# ProPrj_EBS_2026-01-24.net
KiCad netlist of a schematic drawn in EasyEDA Pro
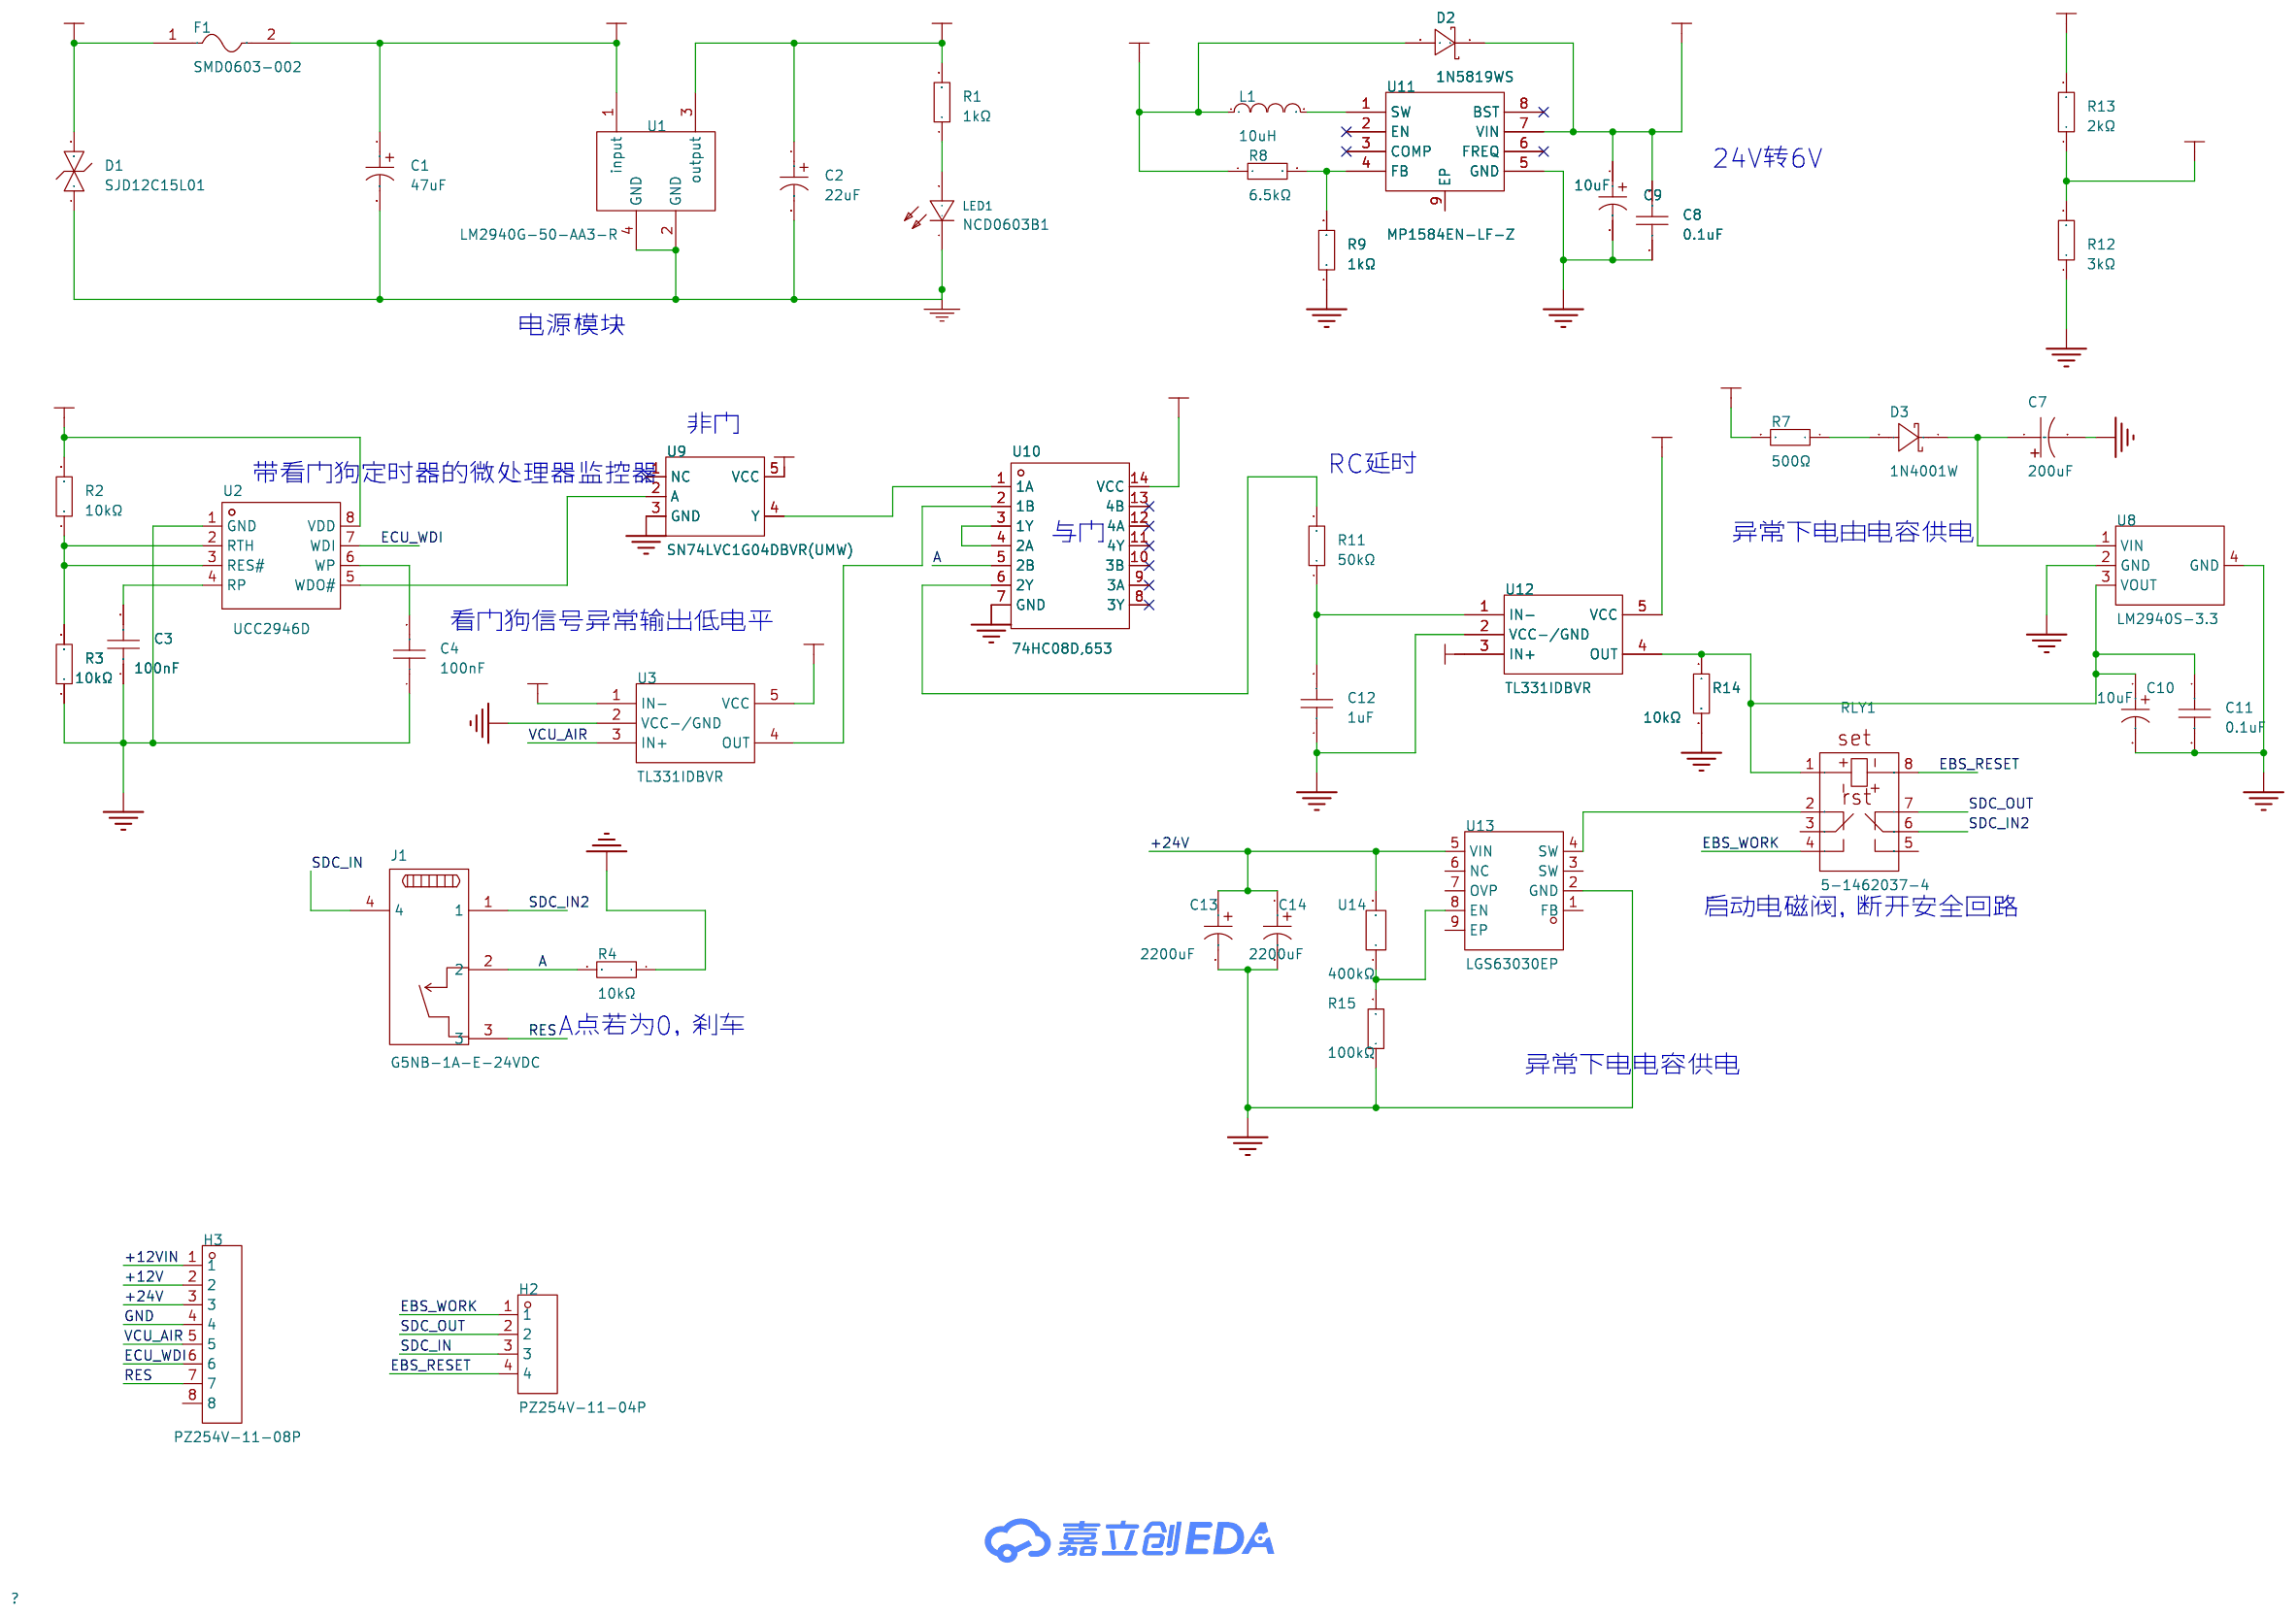
[diagram p0: schematic sheet]

(export (version "E")
  (design (tool "Eeschema 10.0.6"))
  (components
    (comp (ref "C1")
      (value "47uF")
      (footprint "easyedapro:CAP-SMD_BD5.0-L5.3-W5.3-LS5.9-FD")
      (description "容值:47uF;精度:±20%;额定电压:25V;纹波电流:35mA@120Hz;")
      (fields (field (name "Manufacturer Part") "JVJ25V47M5x5") (field (name "Manufacturer") "JIERR(捷而瑞)"))
      (libsource (lib "easyedapro") (part "JVJ25V47M5X5"))
    )
    (comp (ref "C2")
      (value "22uF")
      (footprint "easyedapro:CAP-SMD_BD4.0-L4.3-W4.3-FD_1")
      (description "容值:22uF;精度:±20%;额定电压:16V;纹波电流:20mA@120Hz;")
      (fields (field (name "Manufacturer Part") "JVJ16V22M4X5") (field (name "Manufacturer") "JIERR(捷而瑞)"))
      (libsource (lib "easyedapro") (part "JVJ16V22M4X5"))
    )
    (comp (ref "C3")
      (value "100nF")
      (footprint "easyedapro:C0603")
      (description "容值:100nF;精度:±10%;额定电压:50V;温度系数:X7R;")
      (fields
        (field (name "Manufacturer Part") "CC0603KRX7R9BB104")
        (field (name "Manufacturer") "YAGEO(国巨)")
      )
      (libsource (lib "easyedapro") (part "CC0603KRX7R9BB104"))
    )
    (comp (ref "C4")
      (value "100nF")
      (footprint "easyedapro:C0603")
      (description "容值:100nF;精度:±10%;额定电压:50V;温度系数:X7R;")
      (fields
        (field (name "Manufacturer Part") "CC0603KRX7R9BB104")
        (field (name "Manufacturer") "YAGEO(国巨)")
      )
      (libsource (lib "easyedapro") (part "CC0603KRX7R9BB104"))
    )
    (comp (ref "C7")
      (value "200uF")
      (footprint "easyedapro:CAP-TH_BD12.5-P5.00-D0.6-FD")
      (description "容值:200uF;精度:±20%;额定电压:100V;纹波电流:-;等效串联电阻(ESR):-;")
      (fields (field (name "Manufacturer Part") "LKML1602A201MF") (field (name "Manufacturer") "Ymin(永铭)"))
      (libsource (lib "easyedapro") (part "LKML1602A221MF"))
    )
    (comp (ref "C8")
      (value "0.1uF")
      (footprint "easyedapro:C0603")
      (description "容值:100nF;精度:±10%;额定电压:50V;温度系数:X7R;")
      (fields
        (field (name "Manufacturer Part") "CC0603KRX7R9BB104")
        (field (name "Manufacturer") "YAGEO(国巨)")
      )
      (libsource (lib "easyedapro") (part "CC0603KRX7R9BB104"))
    )
    (comp (ref "C9")
      (value "10uF")
      (footprint "easyedapro:CAP-SMD_BD6.3-L6.6-W6.6-LS7.3-FD-H7.7")
      (description "容值:100uF;精度:±20%;额定电压:50V;纹波电流:140mA@120Hz;")
      (fields (field (name "Manufacturer Part") "JVJ50V100M6x8") (field (name "Manufacturer") "JIERR(捷而瑞)"))
      (libsource (lib "easyedapro") (part "JVJ50V100M6X8"))
    )
    (comp (ref "C10")
      (value "10uF")
      (footprint "easyedapro:CAP-SMD_BD6.3-L6.6-W6.6-LS7.3-FD-H7.7")
      (description "容值:100uF;精度:±20%;额定电压:50V;纹波电流:140mA@120Hz;")
      (fields (field (name "Manufacturer Part") "JVJ50V100M6x8") (field (name "Manufacturer") "JIERR(捷而瑞)"))
      (libsource (lib "easyedapro") (part "JVJ50V100M6X8"))
    )
    (comp (ref "C11")
      (value "0.1uF")
      (footprint "easyedapro:C0603")
      (description "容值:100nF;精度:±10%;额定电压:50V;温度系数:X7R;")
      (fields
        (field (name "Manufacturer Part") "CC0603KRX7R9BB104")
        (field (name "Manufacturer") "YAGEO(国巨)")
      )
      (libsource (lib "easyedapro") (part "CC0603KRX7R9BB104"))
    )
    (comp (ref "C12")
      (value "1uF")
      (footprint "easyedapro:C0603")
      (description "容值:1uF;精度:±10%;额定电压:50V;温度系数:X5R;")
      (fields
        (field (name "Manufacturer Part") "CGA0603X5R105K500JT")
        (field (name "Manufacturer") "HRE(芯声)")
      )
      (libsource (lib "easyedapro") (part "CGA0603X5R105K500JT"))
    )
    (comp (ref "C13")
      (value "2200uF")
      (footprint "easyedapro:CAP-SMD_BD16.0-L17.0-W17.0-FD")
      (description "容值:2200uF;精度:±20%;额定电压:25V;纹波电流:900mA@120Hz;")
      (fields
        (field (name "Manufacturer Part") "JVJ25V2200M16X16")
        (field (name "Manufacturer") "JIERR(捷而瑞)")
      )
      (libsource (lib "easyedapro") (part "JVJ25V2200M16X16"))
    )
    (comp (ref "C14")
      (value "2200uF")
      (footprint "easyedapro:CAP-SMD_BD16.0-L17.0-W17.0-FD")
      (description "容值:2200uF;精度:±20%;额定电压:25V;纹波电流:900mA@120Hz;")
      (fields
        (field (name "Manufacturer Part") "JVJ25V2200M16X16")
        (field (name "Manufacturer") "JIERR(捷而瑞)")
      )
      (libsource (lib "easyedapro") (part "JVJ25V2200M16X16"))
    )
    (comp (ref "D1")
      (value "SJD12C15L01")
      (footprint "easyedapro:SOD-123_L2.7-W1.6-LS3.7-BI")
      (description "反向截止电压(Vrwm):15V;击穿电压(VBR):16.7V;峰值脉冲电流(Ipp)@8/20us:8.2A;钳位电压(Vc)@Ipp:24.4V;")
      (fields (field (name "Manufacturer") "Brightking(君耀电子)"))
      (libsource (lib "easyedapro") (part "SJD12C15L01"))
    )
    (comp (ref "D2")
      (value "1N5819WS")
      (footprint "easyedapro:SOD-323_L1.8-W1.3-LS2.5-RD")
      (description "正向压降(Vf):600mV@1A;直流反向耐压(Vr):40V;整流电流:1A;")
      (fields (field (name "Manufacturer") "Hottech(合科泰)"))
      (libsource (lib "easyedapro") (part "1N5819WS"))
    )
    (comp (ref "D3")
      (value "1N4001W")
      (footprint "easyedapro:SOD-123FL_L2.7-W1.8-LS3.8-RD")
      (description "二极管配置:独立式;正向压降(Vf):1V@1.0A;直流反向耐压(Vr):50V;整流电流:1A;")
      (fields (field (name "Manufacturer") "R+O(宏嘉诚)"))
      (libsource (lib "easyedapro") (part "1N4001W_C18199085"))
    )
    (comp (ref "F1")
      (value "SMD0603-002")
      (footprint "easyedapro:F0603")
      (description "30V,0.02A")
      (fields (field (name "Manufacturer") "台湾陆海"))
      (libsource (lib "easyedapro") (part "SMD0603-002"))
    )
    (comp (ref "H2")
      (value "PZ254V-11-04P")
      (footprint "easyedapro:HDR-TH_4P-P2.54-V-M")
      (fields (field (name "Manufacturer") "XFCN(兴飞)"))
      (libsource (lib "easyedapro") (part "PZ254V-11-04P_C2691448"))
    )
    (comp (ref "H3")
      (value "PZ254V-11-08P")
      (footprint "easyedapro:HDR-TH_8P-P2.54-V-M")
      (fields (field (name "Manufacturer") "XFCN(兴飞)"))
      (libsource (lib "easyedapro") (part "PZ254V-11-08P"))
    )
    (comp (ref "J1")
      (value "G5NB-1A-E-24VDC")
      (footprint "easyedapro:RELAY-TH_G5NB-1A-E-24VDC")
      (description "线圈电压:24V;触点形式:一组常开:1A(单刀单掷-常开);触点容量(电阻负载):5A@250VAC；3A@30VDC;最大切换电压:250V@AC；30V@DC;最大切换电流:5A;")
      (fields (field (name "Manufacturer") "OMRON(欧姆龙)"))
      (libsource (lib "easyedapro") (part "G5NB-1A-E-24VDC"))
    )
    (comp (ref "L1")
      (value "10uH")
      (footprint "easyedapro:IND-SMD_L4.0-W4.0")
      (description "电感值:10uH;精度:±20%;额定电流:2.35A;饱和电流(Isat):3.5A;类型:-;")
      (fields
        (field (name "Manufacturer Part") "FHD4020S-100MT")
        (field (name "Manufacturer") "cjiang(长江微电)")
      )
      (libsource (lib "easyedapro") (part "FHD4020S-100MT"))
    )
    (comp (ref "LED1")
      (value "NCD0603B1")
      (footprint "easyedapro:LED0603-RD")
      (description "发光颜色:蓝灯;")
      (fields (field (name "Manufacturer") "国星光电"))
      (libsource (lib "easyedapro") (part "FC-DA1608BK-470H10"))
    )
    (comp (ref "R1")
      (value "1kΩ")
      (footprint "easyedapro:R0603")
      (description "电阻类型:厚膜电阻;阻值:1kΩ;精度:±1%;功率:100mW;")
      (fields
        (field (name "Manufacturer Part") "0603WAF1001T5E")
        (field (name "Manufacturer") "UNI-ROYAL(厚声)")
      )
      (libsource (lib "easyedapro") (part "0603WAF1001T5E"))
    )
    (comp (ref "R2")
      (value "10kΩ")
      (footprint "easyedapro:R0603")
      (description "电阻类型:厚膜电阻;阻值:10kΩ;精度:±1%;功率:100mW;工作电压:75V;温度系数:±100ppm/°C;")
      (fields
        (field (name "Manufacturer Part") "0603WAF1002T5E")
        (field (name "Manufacturer") "UNI-ROYAL(厚声)")
      )
      (libsource (lib "easyedapro") (part "0603WAF1002T5E"))
    )
    (comp (ref "R3")
      (value "10kΩ")
      (footprint "easyedapro:R0603")
      (description "电阻类型:厚膜电阻;阻值:10kΩ;精度:±1%;功率:100mW;工作电压:75V;温度系数:±100ppm/°C;")
      (fields
        (field (name "Manufacturer Part") "0603WAF1002T5E")
        (field (name "Manufacturer") "UNI-ROYAL(厚声)")
      )
      (libsource (lib "easyedapro") (part "0603WAF1002T5E"))
    )
    (comp (ref "R4")
      (value "10kΩ")
      (footprint "easyedapro:R0603")
      (description "电阻类型:厚膜电阻;阻值:1kΩ;精度:±1%;功率:100mW;")
      (fields
        (field (name "Manufacturer Part") "0603WAF1001T5E")
        (field (name "Manufacturer") "UNI-ROYAL(厚声)")
      )
      (libsource (lib "easyedapro") (part "0603WAF1001T5E"))
    )
    (comp (ref "R7")
      (value "500Ω")
      (footprint "easyedapro:R0603")
      (description "电阻类型:厚膜电阻;阻值:1kΩ;精度:±1%;功率:100mW;")
      (fields
        (field (name "Manufacturer Part") "0603WAF1001T5E")
        (field (name "Manufacturer") "UNI-ROYAL(厚声)")
      )
      (libsource (lib "easyedapro") (part "0603WAF1001T5E"))
    )
    (comp (ref "R8")
      (value "6.5kΩ")
      (footprint "easyedapro:R0603")
      (description "电阻类型:厚膜电阻;阻值:1kΩ;精度:±1%;功率:100mW;")
      (fields
        (field (name "Manufacturer Part") "0603WAF1001T5E")
        (field (name "Manufacturer") "UNI-ROYAL(厚声)")
      )
      (libsource (lib "easyedapro") (part "0603WAF1001T5E"))
    )
    (comp (ref "R9")
      (value "1kΩ")
      (footprint "easyedapro:R0603")
      (description "电阻类型:厚膜电阻;阻值:1kΩ;精度:±1%;功率:100mW;")
      (fields
        (field (name "Manufacturer Part") "0603WAF1001T5E")
        (field (name "Manufacturer") "UNI-ROYAL(厚声)")
      )
      (libsource (lib "easyedapro") (part "0603WAF1001T5E"))
    )
    (comp (ref "R11")
      (value "50kΩ")
      (footprint "easyedapro:R0603")
      (description "电阻类型:薄膜电阻;阻值:50kΩ;精度:±0.1%;功率:62.5mW;工作电压:50V;温度系数:±25ppm/°C;")
      (fields (field (name "Manufacturer Part") "AR03BTC5002A") (field (name "Manufacturer") "Viking(光颉)"))
      (libsource (lib "easyedapro") (part "AR03BTC5002A"))
    )
    (comp (ref "R12")
      (value "3kΩ")
      (footprint "easyedapro:R0603")
      (description "电阻类型:厚膜电阻;阻值:3kΩ;精度:±1%;功率:100mW;工作电压:75V;温度系数:±100ppm/°C;")
      (fields
        (field (name "Manufacturer Part") "0603WAF3001T5E")
        (field (name "Manufacturer") "UNI-ROYAL(厚声)")
      )
      (libsource (lib "easyedapro") (part "0603WAF3001T5E"))
    )
    (comp (ref "R13")
      (value "2kΩ")
      (footprint "easyedapro:R0603")
      (description "电阻类型:厚膜电阻;阻值:2kΩ;精度:±1%;功率:100mW;工作电压:75V;温度系数:±100ppm/°C;")
      (fields
        (field (name "Manufacturer Part") "0603WAF2001T5E")
        (field (name "Manufacturer") "UNI-ROYAL(厚声)")
      )
      (libsource (lib "easyedapro") (part "0603WAF2001T5E"))
    )
    (comp (ref "R14")
      (value "10kΩ")
      (footprint "easyedapro:R0603")
      (description "电阻类型:厚膜电阻;阻值:10kΩ;精度:±1%;功率:100mW;工作电压:75V;温度系数:±100ppm/°C;")
      (fields
        (field (name "Manufacturer Part") "0603WAF1002T5E")
        (field (name "Manufacturer") "UNI-ROYAL(厚声)")
      )
      (libsource (lib "easyedapro") (part "0603WAF1002T5E"))
    )
    (comp (ref "R15")
      (value "100kΩ")
      (footprint "easyedapro:R0603")
      (description "电阻类型:厚膜电阻;阻值:100kΩ;精度:±1%;功率:100mW;工作电压:75V;温度系数:±100ppm/°C;")
      (fields
        (field (name "Manufacturer Part") "0603WAF1003T5E")
        (field (name "Manufacturer") "UNI-ROYAL(厚声)")
      )
      (libsource (lib "easyedapro") (part "0603WAF1003T5E"))
    )
    (comp (ref "RLY1")
      (value "5-1462037-4")
      (footprint "easyedapro:RELAY-SMD_8P-L10.0-W6.0_IM43GR")
      (description "线圈电压:3V;触点形式:两组转换:2C(双刀双掷-转换);触点容量(电阻负载):-;最大切换电压:250V@AC；220V@DC;最大切换电流:2A;")
      (fields (field (name "Manufacturer") "TE Connectivity(泰科电子)"))
      (libsource (lib "easyedapro") (part "5-1462037-4"))
    )
    (comp (ref "U1")
      (value "LM2940G-50-AA3-R")
      (footprint "easyedapro:SOT-223-4_L6.5-W3.5-P2.30-LS7.0-BR")
      (description "输出类型:固定;输出极性:正;输出通道数:1;最大输入电压:26V;输出电压:5V;压差:800mV@(1A);输出电流:1A;电源纹波抑制比(PSRR):72dB@(120Hz);")
      (fields (field (name "Manufacturer") "UTC(友顺)"))
      (libsource (lib "easyedapro") (part "LM2940G-50-AA3-R"))
    )
    (comp (ref "U2")
      (value "UCC2946D")
      (footprint "easyedapro:SOIC-8_L4.9-W3.9-P1.27-LS6.0-BL")
      (description "UCC2946 带看门狗定时器的微处理器监控器")
      (fields (field (name "Manufacturer") "TI(德州仪器)"))
      (libsource (lib "easyedapro") (part "UCC2946D"))
    )
    (comp (ref "U3")
      (value "TL331IDBVR")
      (footprint "easyedapro:SOT-23-5_L3.0-W1.7-P0.95-LS2.8-BR")
      (description "比较器数:单路;输入失调电压(Vos):2mV;输入偏置电流(Ib):25nA;轨到轨:轨到轨输入;")
      (fields (field (name "Manufacturer") "TI(德州仪器)"))
      (libsource (lib "easyedapro") (part "TL331IDBVR"))
    )
    (comp (ref "U8")
      (value "LM2940S-3.3")
      (footprint "easyedapro:SOT-223-3_L6.5-W3.4-P2.30-LS7.0-BR")
      (description "输出类型:固定;工作电压:26V;输出电压:3.3V;输出电流:1A;电源纹波抑制比(PSRR):-;输出极性:正极;")
      (fields (field (name "Manufacturer") "HTC"))
      (libsource (lib "easyedapro") (part "LM2940S-3.3"))
    )
    (comp (ref "U9")
      (value "SN74LVC1G04DBVR(UMW)")
      (footprint "easyedapro:SOT-23-5_L3.0-W1.7-P0.95-LS2.8-BR")
      (description "工作电压:1.65V~5.5V;静态电流(Iq):10uA;")
      (fields (field (name "Manufacturer") "UMW(友台半导体)"))
      (libsource (lib "easyedapro") (part "SN74LVC1G04DBVR_C434067"))
    )
    (comp (ref "U10")
      (value "74HC08D,653")
      (footprint "easyedapro:SOIC-14_L8.7-W3.9-P1.27-LS6.0-BL")
      (description "逻辑类型:与门;通道数:4;工作电压:2V~6V;静态电流(Iq):2uA;传播延迟(tpd):27ns@4.5V,50pF;")
      (fields (field (name "Manufacturer") "Nexperia(安世)"))
      (libsource (lib "easyedapro") (part "74HC08D,653"))
    )
    (comp (ref "U11")
      (value "MP1584EN-LF-Z")
      (footprint "easyedapro:SOIC-8_L5.0-W4.0-P1.27-LS6.0-BL-EP2.0")
      (description "功能类型:降压型;工作电压:4.5V~28V;输出电压:800mV~25V;输出电流:3A;输出类型:可调;")
      (fields (field (name "Manufacturer") "MPS(芯源)"))
      (libsource (lib "easyedapro") (part "MP1584EN-LF-Z"))
    )
    (comp (ref "U12")
      (value "TL331IDBVR")
      (footprint "easyedapro:SOT-23-5_L3.0-W1.7-P0.95-LS2.8-BR")
      (description "比较器数:单路;输入失调电压(Vos):2mV;输入偏置电流(Ib):25nA;轨到轨:轨到轨输入;")
      (fields (field (name "Manufacturer") "TI(德州仪器)"))
      (libsource (lib "easyedapro") (part "TL331IDBVR"))
    )
    (comp (ref "U13")
      (value "LGS63030EP")
      (footprint "easyedapro:SOP-8_L4.9-W3.9-P1.27-LS6.0-TL-EP")
      (description "类型:DC-DC恒流驱动;输入电压:3V~60V;开关频率:1.2MHz;通道数:1;输出电压:3V~60V;输出电流:500mA;调光:模拟;拓扑结构:升压;")
      (fields (field (name "Manufacturer") "Legend-Si(棱晶半导体)"))
      (libsource (lib "easyedapro") (part "LGS63030EP"))
    )
    (comp (ref "U14")
      (value "400kΩ")
      (footprint "easyedapro:R0805")
      (description "阻值:400kΩ;精度:±0.1%;功率:125mW;温度系数:±25ppm/°C;")
      (fields (field (name "Manufacturer Part") "AR05BTCW4003") (field (name "Manufacturer") "Viking(光颉)"))
      (libsource (lib "easyedapro") (part "AR05BTCW4003"))
    )
  )
  (nets
    (net (code "1") (name "+3V") (class "Default")
      (node (ref "R12") (pin "2") (pinfunction "2_2") (pintype "input"))
      (node (ref "R13") (pin "1") (pinfunction "1_1") (pintype "input"))
      (node (ref "U12") (pin "3") (pinfunction "IN+_3") (pintype "unspecified"))
      (node (ref "U12") (pin "5") (pinfunction "VCC_5") (pintype "unspecified"))
    )
    (net (code "2") (name "+5V") (class "Default")
      (node (ref "C2") (pin "1") (pinfunction "1_1") (pintype "input"))
      (node (ref "R1") (pin "2") (pinfunction "2_2") (pintype "input"))
      (node (ref "R13") (pin "2") (pinfunction "2_2") (pintype "input"))
      (node (ref "R2") (pin "2") (pinfunction "2_2") (pintype "input"))
      (node (ref "U1") (pin "3") (pinfunction "output_3") (pintype "input"))
      (node (ref "U10") (pin "14") (pinfunction "VCC_14") (pintype "unspecified"))
      (node (ref "U2") (pin "8") (pinfunction "VDD_8") (pintype "input"))
      (node (ref "U3") (pin "5") (pinfunction "VCC_5") (pintype "unspecified"))
      (node (ref "U9") (pin "5") (pinfunction "VCC_5") (pintype "unspecified"))
    )
    (net (code "3") (name "+6V") (class "Default")
      (node (ref "D2") (pin "2") (pinfunction "A_2") (pintype "unspecified"))
      (node (ref "L1") (pin "1") (pinfunction "1_1") (pintype "unspecified"))
      (node (ref "R8") (pin "1") (pinfunction "1_1") (pintype "input"))
      (node (ref "U3") (pin "1") (pinfunction "IN-_1") (pintype "unspecified"))
    )
    (net (code "4") (name "+12V") (class "Default")
      (node (ref "C1") (pin "1") (pinfunction "1_1") (pintype "input"))
      (node (ref "F1") (pin "2") (pinfunction "2_2") (pintype "input"))
      (node (ref "H3") (pin "2") (pinfunction "2_2") (pintype "unspecified"))
      (node (ref "R7") (pin "2") (pinfunction "2_2") (pintype "input"))
      (node (ref "U1") (pin "1") (pinfunction "input_1") (pintype "input"))
    )
    (net (code "5") (name "+24V") (class "Default")
      (node (ref "C13") (pin "1") (pinfunction "1_1") (pintype "input"))
      (node (ref "C14") (pin "1") (pinfunction "1_1") (pintype "input"))
      (node (ref "C8") (pin "1") (pinfunction "1_1") (pintype "unspecified"))
      (node (ref "C9") (pin "1") (pinfunction "1_1") (pintype "input"))
      (node (ref "D2") (pin "1") (pinfunction "K_1") (pintype "unspecified"))
      (node (ref "H3") (pin "3") (pinfunction "3_3") (pintype "unspecified"))
      (node (ref "U11") (pin "7") (pinfunction "VIN_7") (pintype "unspecified"))
      (node (ref "U13") (pin "5") (pinfunction "VIN_5") (pintype "unspecified"))
      (node (ref "U14") (pin "2") (pinfunction "2_2") (pintype "unspecified"))
    )
    (net (code "6") (name "/+12VIN") (class "Default")
      (node (ref "H3") (pin "1") (pinfunction "1_1") (pintype "unspecified"))
    )
    (net (code "7") (name "/A") (class "Default")
      (node (ref "J1") (pin "2") (pinfunction "2_2") (pintype "unspecified"))
      (node (ref "R4") (pin "2") (pinfunction "2_2") (pintype "input"))
      (node (ref "U10") (pin "5") (pinfunction "2B_5") (pintype "unspecified"))
    )
    (net (code "8") (name "/EBS_RESET") (class "Default")
      (node (ref "H2") (pin "4") (pinfunction "4_4") (pintype "unspecified"))
      (node (ref "RLY1") (pin "8") (pinfunction "8_8") (pintype "unspecified"))
    )
    (net (code "9") (name "/EBS_WORK") (class "Default")
      (node (ref "H2") (pin "1") (pinfunction "1_1") (pintype "unspecified"))
      (node (ref "RLY1") (pin "4") (pinfunction "4_4") (pintype "unspecified"))
    )
    (net (code "10") (name "/ECU_WDI") (class "Default")
      (node (ref "H3") (pin "6") (pinfunction "6_6") (pintype "unspecified"))
      (node (ref "U2") (pin "7") (pinfunction "WDI_7") (pintype "input"))
    )
    (net (code "11") (name "/RES") (class "Default")
      (node (ref "H3") (pin "7") (pinfunction "7_7") (pintype "unspecified"))
      (node (ref "J1") (pin "3") (pinfunction "3_3") (pintype "unspecified"))
    )
    (net (code "12") (name "/SDC_IN") (class "Default")
      (node (ref "H2") (pin "3") (pinfunction "3_3") (pintype "unspecified"))
      (node (ref "J1") (pin "4") (pinfunction "4_4") (pintype "unspecified"))
    )
    (net (code "13") (name "/SDC_IN2") (class "Default")
      (node (ref "J1") (pin "1") (pinfunction "1_1") (pintype "unspecified"))
      (node (ref "RLY1") (pin "6") (pinfunction "6_6") (pintype "unspecified"))
    )
    (net (code "14") (name "/SDC_OUT") (class "Default")
      (node (ref "H2") (pin "2") (pinfunction "2_2") (pintype "unspecified"))
      (node (ref "RLY1") (pin "7") (pinfunction "7_7") (pintype "unspecified"))
    )
    (net (code "15") (name "/VCU_AIR") (class "Default")
      (node (ref "H3") (pin "5") (pinfunction "5_5") (pintype "unspecified"))
      (node (ref "U3") (pin "3") (pinfunction "IN+_3") (pintype "unspecified"))
    )
    (net (code "16") (name "12VIN") (class "Default")
      (node (ref "D1") (pin "2") (pinfunction "2_2") (pintype "input"))
      (node (ref "F1") (pin "1") (pinfunction "1_1") (pintype "input"))
    )
    (net (code "17") (name "GND") (class "Default")
      (node (ref "C1") (pin "2") (pinfunction "2_2") (pintype "input"))
      (node (ref "C10") (pin "2") (pinfunction "2_2") (pintype "input"))
      (node (ref "C11") (pin "2") (pinfunction "2_2") (pintype "unspecified"))
      (node (ref "C12") (pin "1") (pinfunction "1_1") (pintype "unspecified"))
      (node (ref "C13") (pin "2") (pinfunction "2_2") (pintype "input"))
      (node (ref "C14") (pin "2") (pinfunction "2_2") (pintype "input"))
      (node (ref "C2") (pin "2") (pinfunction "2_2") (pintype "input"))
      (node (ref "C3") (pin "1") (pinfunction "1_1") (pintype "unspecified"))
      (node (ref "C4") (pin "1") (pinfunction "1_1") (pintype "unspecified"))
      (node (ref "C7") (pin "2") (pinfunction "2_2") (pintype "unspecified"))
      (node (ref "C8") (pin "2") (pinfunction "2_2") (pintype "unspecified"))
      (node (ref "C9") (pin "2") (pinfunction "2_2") (pintype "input"))
      (node (ref "D1") (pin "1") (pinfunction "1_1") (pintype "input"))
      (node (ref "H3") (pin "4") (pinfunction "4_4") (pintype "unspecified"))
      (node (ref "LED1") (pin "1") (pinfunction "-_1") (pintype "input"))
      (node (ref "R12") (pin "1") (pinfunction "1_1") (pintype "input"))
      (node (ref "R14") (pin "2") (pinfunction "2_2") (pintype "input"))
      (node (ref "R15") (pin "1") (pinfunction "1_1") (pintype "input"))
      (node (ref "R3") (pin "1") (pinfunction "1_1") (pintype "input"))
      (node (ref "R4") (pin "1") (pinfunction "1_1") (pintype "input"))
      (node (ref "R9") (pin "1") (pinfunction "1_1") (pintype "input"))
      (node (ref "U1") (pin "2") (pinfunction "GND_2") (pintype "input"))
      (node (ref "U1") (pin "4") (pinfunction "GND_4") (pintype "input"))
      (node (ref "U10") (pin "7") (pinfunction "GND_7") (pintype "unspecified"))
      (node (ref "U11") (pin "5") (pinfunction "GND_5") (pintype "unspecified"))
      (node (ref "U12") (pin "2") (pinfunction "VCC-/GND_2") (pintype "unspecified"))
      (node (ref "U13") (pin "2") (pinfunction "GND_2") (pintype "unspecified"))
      (node (ref "U2") (pin "1") (pinfunction "GND_1") (pintype "input"))
      (node (ref "U3") (pin "2") (pinfunction "VCC-/GND_2") (pintype "unspecified"))
      (node (ref "U8") (pin "2") (pinfunction "GND_2") (pintype "unspecified"))
      (node (ref "U8") (pin "4") (pinfunction "GND_4") (pintype "unspecified"))
      (node (ref "U9") (pin "3") (pinfunction "GND_3") (pintype "unspecified"))
    )
    (net (code "18") (name "Net-(D3-A)") (class "Default")
      (node (ref "D3") (pin "2") (pinfunction "A_2") (pintype "unspecified"))
      (node (ref "R7") (pin "1") (pinfunction "1_1") (pintype "input"))
    )
    (net (code "19") (name "Net-(D3-K)") (class "Default")
      (node (ref "C7") (pin "1") (pinfunction "1_1") (pintype "unspecified"))
      (node (ref "D3") (pin "1") (pinfunction "K_1") (pintype "unspecified"))
      (node (ref "U8") (pin "1") (pinfunction "VIN_1") (pintype "unspecified"))
    )
    (net (code "20") (name "Net-(LED1-+)") (class "Default")
      (node (ref "LED1") (pin "2") (pinfunction "+_2") (pintype "input"))
      (node (ref "R1") (pin "1") (pinfunction "1_1") (pintype "input"))
    )
    (net (code "21") (name "Net-(RLY1-Pad2)") (class "Default")
      (node (ref "RLY1") (pin "2") (pinfunction "2_2") (pintype "unspecified"))
      (node (ref "U13") (pin "4") (pinfunction "SW_4") (pintype "unspecified"))
    )
    (net (code "22") (name "Net-(U2-RES#)") (class "Default")
      (node (ref "R2") (pin "1") (pinfunction "1_1") (pintype "input"))
      (node (ref "R3") (pin "2") (pinfunction "2_2") (pintype "input"))
      (node (ref "U2") (pin "2") (pinfunction "RTH_2") (pintype "input"))
      (node (ref "U2") (pin "3") (pinfunction "RES#_3") (pintype "input"))
    )
    (net (code "23") (name "Net-(U2-RP)") (class "Default")
      (node (ref "C3") (pin "2") (pinfunction "2_2") (pintype "unspecified"))
      (node (ref "U2") (pin "4") (pinfunction "RP_4") (pintype "input"))
    )
    (net (code "24") (name "Net-(U2-WDO#)") (class "Default")
      (node (ref "U2") (pin "5") (pinfunction "WDO#_5") (pintype "input"))
      (node (ref "U9") (pin "2") (pinfunction "A_2") (pintype "unspecified"))
    )
    (net (code "25") (name "Net-(U2-WP)") (class "Default")
      (node (ref "C4") (pin "2") (pinfunction "2_2") (pintype "unspecified"))
      (node (ref "U2") (pin "6") (pinfunction "WP_6") (pintype "input"))
    )
    (net (code "26") (name "Net-(U10-1A)") (class "Default")
      (node (ref "U10") (pin "1") (pinfunction "1A_1") (pintype "unspecified"))
      (node (ref "U9") (pin "4") (pinfunction "Y_4") (pintype "unspecified"))
    )
    (net (code "27") (name "Net-(U10-1B)") (class "Default")
      (node (ref "U10") (pin "2") (pinfunction "1B_2") (pintype "unspecified"))
      (node (ref "U3") (pin "4") (pinfunction "OUT_4") (pintype "unspecified"))
    )
    (net (code "28") (name "Net-(U10-1Y)") (class "Default")
      (node (ref "U10") (pin "3") (pinfunction "1Y_3") (pintype "unspecified"))
      (node (ref "U10") (pin "4") (pinfunction "2A_4") (pintype "unspecified"))
    )
    (net (code "29") (name "Net-(U10-2Y)") (class "Default")
      (node (ref "R11") (pin "2") (pinfunction "2_2") (pintype "unspecified"))
      (node (ref "U10") (pin "6") (pinfunction "2Y_6") (pintype "unspecified"))
    )
    (net (code "30") (name "Net-(U11-FB)") (class "Default")
      (node (ref "R8") (pin "2") (pinfunction "2_2") (pintype "input"))
      (node (ref "R9") (pin "2") (pinfunction "2_2") (pintype "input"))
      (node (ref "U11") (pin "4") (pinfunction "FB_4") (pintype "unspecified"))
    )
    (net (code "31") (name "Net-(U11-SW)") (class "Default")
      (node (ref "L1") (pin "2") (pinfunction "2_2") (pintype "unspecified"))
      (node (ref "U11") (pin "1") (pinfunction "SW_1") (pintype "unspecified"))
    )
    (net (code "32") (name "Net-(U12-IN-)") (class "Default")
      (node (ref "C12") (pin "2") (pinfunction "2_2") (pintype "unspecified"))
      (node (ref "R11") (pin "1") (pinfunction "1_1") (pintype "unspecified"))
      (node (ref "U12") (pin "1") (pinfunction "IN-_1") (pintype "unspecified"))
    )
    (net (code "33") (name "Net-(U12-OUT)") (class "Default")
      (node (ref "C10") (pin "1") (pinfunction "1_1") (pintype "input"))
      (node (ref "C11") (pin "1") (pinfunction "1_1") (pintype "unspecified"))
      (node (ref "R14") (pin "1") (pinfunction "1_1") (pintype "input"))
      (node (ref "RLY1") (pin "1") (pinfunction "1_1") (pintype "unspecified"))
      (node (ref "U12") (pin "4") (pinfunction "OUT_4") (pintype "unspecified"))
      (node (ref "U8") (pin "3") (pinfunction "VOUT_3") (pintype "unspecified"))
    )
    (net (code "34") (name "Net-(U13-EN)") (class "Default")
      (node (ref "R15") (pin "2") (pinfunction "2_2") (pintype "input"))
      (node (ref "U13") (pin "8") (pinfunction "EN_8") (pintype "unspecified"))
      (node (ref "U14") (pin "1") (pinfunction "1_1") (pintype "unspecified"))
    )
    (net (code "35") (name "unconnected-(H3-Pad8)") (class "Default")
      (node (ref "H3") (pin "8") (pinfunction "8_8") (pintype "unspecified"))
    )
    (net (code "36") (name "unconnected-(RLY1-Pad3)") (class "Default")
      (node (ref "RLY1") (pin "3") (pinfunction "3_3") (pintype "unspecified"))
    )
    (net (code "37") (name "unconnected-(RLY1-Pad5)") (class "Default")
      (node (ref "RLY1") (pin "5") (pinfunction "5_5") (pintype "unspecified"))
    )
    (net (code "38") (name "unconnected-(U9-NC-Pad1)") (class "Default")
      (node (ref "U9") (pin "1") (pinfunction "NC_1") (pintype "unspecified+no_connect"))
    )
    (net (code "39") (name "unconnected-(U10-3A-Pad9)") (class "Default")
      (node (ref "U10") (pin "9") (pinfunction "3A_9") (pintype "unspecified+no_connect"))
    )
    (net (code "40") (name "unconnected-(U10-3B-Pad10)") (class "Default")
      (node (ref "U10") (pin "10") (pinfunction "3B_10") (pintype "unspecified+no_connect"))
    )
    (net (code "41") (name "unconnected-(U10-3Y-Pad8)") (class "Default")
      (node (ref "U10") (pin "8") (pinfunction "3Y_8") (pintype "unspecified+no_connect"))
    )
    (net (code "42") (name "unconnected-(U10-4A-Pad12)") (class "Default")
      (node (ref "U10") (pin "12") (pinfunction "4A_12") (pintype "unspecified+no_connect"))
    )
    (net (code "43") (name "unconnected-(U10-4B-Pad13)") (class "Default")
      (node (ref "U10") (pin "13") (pinfunction "4B_13") (pintype "unspecified+no_connect"))
    )
    (net (code "44") (name "unconnected-(U10-4Y-Pad11)") (class "Default")
      (node (ref "U10") (pin "11") (pinfunction "4Y_11") (pintype "unspecified+no_connect"))
    )
    (net (code "45") (name "unconnected-(U11-BST-Pad8)") (class "Default")
      (node (ref "U11") (pin "8") (pinfunction "BST_8") (pintype "unspecified+no_connect"))
    )
    (net (code "46") (name "unconnected-(U11-COMP-Pad3)") (class "Default")
      (node (ref "U11") (pin "3") (pinfunction "COMP_3") (pintype "unspecified+no_connect"))
    )
    (net (code "47") (name "unconnected-(U11-EN-Pad2)") (class "Default")
      (node (ref "U11") (pin "2") (pinfunction "EN_2") (pintype "unspecified+no_connect"))
    )
    (net (code "48") (name "unconnected-(U11-EP-Pad9)") (class "Default")
      (node (ref "U11") (pin "9") (pinfunction "EP_9") (pintype "unspecified"))
    )
    (net (code "49") (name "unconnected-(U11-FREQ-Pad6)") (class "Default")
      (node (ref "U11") (pin "6") (pinfunction "FREQ_6") (pintype "unspecified+no_connect"))
    )
    (net (code "50") (name "unconnected-(U13-EP-Pad9)") (class "Default")
      (node (ref "U13") (pin "9") (pinfunction "EP_9") (pintype "unspecified"))
    )
    (net (code "51") (name "unconnected-(U13-FB-Pad1)") (class "Default")
      (node (ref "U13") (pin "1") (pinfunction "FB_1") (pintype "unspecified"))
    )
    (net (code "52") (name "unconnected-(U13-NC-Pad6)") (class "Default")
      (node (ref "U13") (pin "6") (pinfunction "NC_6") (pintype "unspecified"))
    )
    (net (code "53") (name "unconnected-(U13-OVP-Pad7)") (class "Default")
      (node (ref "U13") (pin "7") (pinfunction "OVP_7") (pintype "unspecified"))
    )
    (net (code "54") (name "unconnected-(U13-SW-Pad3)") (class "Default")
      (node (ref "U13") (pin "3") (pinfunction "SW_3") (pintype "unspecified"))
    )
  )
)
